# prg.net
KiCad netlist of a schematic drawn in EAGLE
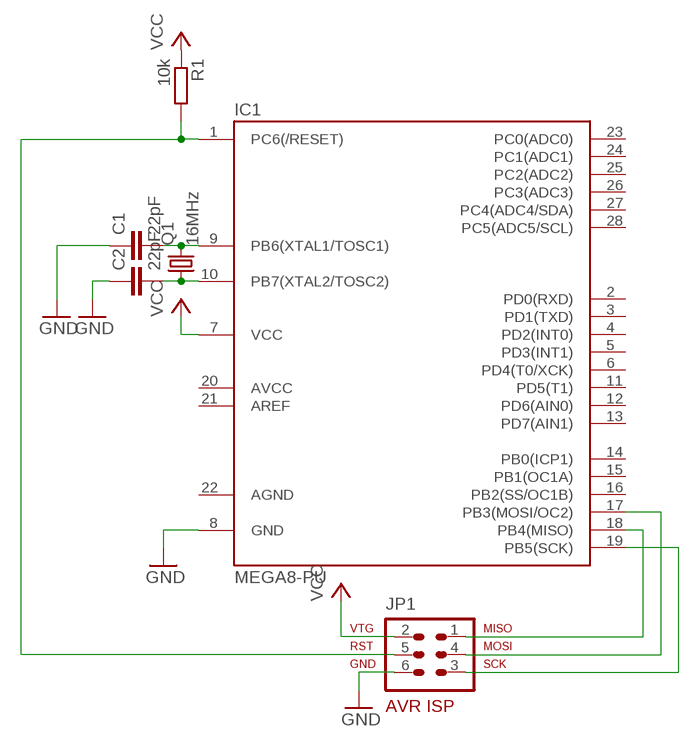
[diagram p0: schematic, sheet 1]

(export (version "E")
  (design (tool "Eeschema 10.0.6"))
  (components
    (comp (ref "C1")
      (value "22pF")
      (footprint "eagle-import:C025-025X050")
      (libsource (lib "eagle-import") (part "C-EU025-025X050"))
    )
    (comp (ref "C2")
      (value "22pF")
      (footprint "eagle-import:C050-025X075")
      (libsource (lib "eagle-import") (part "C-EU050-025X075"))
    )
    (comp (ref "IC1")
      (value "MEGA8-PU")
      (footprint "eagle-import:DIL28-3")
      (libsource (lib "eagle-import") (part "MEGA8-PU"))
    )
    (comp (ref "JP1")
      (value "AVR-ISP-6")
      (footprint "eagle-import:AVR-ISP-6")
      (libsource (lib "eagle-import") (part "AVR-ISP-6"))
    )
    (comp (ref "Q1")
      (value "16MHz")
      (footprint "eagle-import:HC49_S")
      (libsource (lib "eagle-import") (part "CRYSTALHC49S"))
    )
    (comp (ref "R1")
      (value "10k")
      (footprint "eagle-import:0204_7")
      (libsource (lib "eagle-import") (part "R-EU_0204/7"))
    )
  )
  (nets
    (net (code "1") (name "/AGND") (class "Default")
      (node (ref "IC1") (pin "22") (pinfunction "AGND_22") (pintype "power_in"))
    )
    (net (code "2") (name "GND") (class "Default")
      (node (ref "C1") (pin "1") (pinfunction "1_1") (pintype "passive"))
      (node (ref "C2") (pin "1") (pinfunction "1_1") (pintype "passive"))
      (node (ref "IC1") (pin "8") (pinfunction "GND_8") (pintype "power_in"))
      (node (ref "JP1") (pin "6") (pinfunction "6_6") (pintype "passive"))
    )
    (net (code "3") (name "Net-(IC1-PB3(MOSI{slash}OC2))") (class "Default")
      (node (ref "IC1") (pin "17") (pinfunction "PB3(MOSI/OC2)_17") (pintype "bidirectional"))
      (node (ref "JP1") (pin "4") (pinfunction "4_4") (pintype "passive"))
    )
    (net (code "4") (name "Net-(IC1-PB4(MISO))") (class "Default")
      (node (ref "IC1") (pin "18") (pinfunction "PB4(MISO)_18") (pintype "bidirectional"))
      (node (ref "JP1") (pin "1") (pinfunction "1_1") (pintype "passive"))
    )
    (net (code "5") (name "Net-(IC1-PB5(SCK))") (class "Default")
      (node (ref "IC1") (pin "19") (pinfunction "PB5(SCK)_19") (pintype "bidirectional"))
      (node (ref "JP1") (pin "3") (pinfunction "3_3") (pintype "passive"))
    )
    (net (code "6") (name "Net-(IC1-PB6(XTAL1{slash}TOSC1))") (class "Default")
      (node (ref "C1") (pin "2") (pinfunction "2_2") (pintype "passive"))
      (node (ref "IC1") (pin "9") (pinfunction "PB6(XTAL1/TOSC1)_9") (pintype "bidirectional"))
      (node (ref "Q1") (pin "2") (pinfunction "2_2") (pintype "passive"))
    )
    (net (code "7") (name "Net-(IC1-PB7(XTAL2{slash}TOSC2))") (class "Default")
      (node (ref "C2") (pin "2") (pinfunction "2_2") (pintype "passive"))
      (node (ref "IC1") (pin "10") (pinfunction "PB7(XTAL2/TOSC2)_10") (pintype "bidirectional"))
      (node (ref "Q1") (pin "1") (pinfunction "1_1") (pintype "passive"))
    )
    (net (code "8") (name "Net-(IC1-PC6({slash}RESET))") (class "Default")
      (node (ref "IC1") (pin "1") (pinfunction "PC6(/RESET)_1") (pintype "bidirectional"))
      (node (ref "JP1") (pin "5") (pinfunction "5_5") (pintype "passive"))
      (node (ref "R1") (pin "2") (pinfunction "2_2") (pintype "passive"))
    )
    (net (code "9") (name "VCC") (class "Default")
      (node (ref "IC1") (pin "7") (pinfunction "VCC_7") (pintype "power_in"))
      (node (ref "JP1") (pin "2") (pinfunction "2_2") (pintype "passive"))
      (node (ref "R1") (pin "1") (pinfunction "1_1") (pintype "passive"))
    )
    (net (code "10") (name "unconnected-(IC1-AREF-Pad21)") (class "Default")
      (node (ref "IC1") (pin "21") (pinfunction "AREF_21") (pintype "passive"))
    )
    (net (code "11") (name "unconnected-(IC1-AVCC-Pad20)") (class "Default")
      (node (ref "IC1") (pin "20") (pinfunction "AVCC_20") (pintype "passive"))
    )
    (net (code "12") (name "unconnected-(IC1-PB0(ICP1)-Pad14)") (class "Default")
      (node (ref "IC1") (pin "14") (pinfunction "PB0(ICP1)_14") (pintype "bidirectional"))
    )
    (net (code "13") (name "unconnected-(IC1-PB1(OC1A)-Pad15)") (class "Default")
      (node (ref "IC1") (pin "15") (pinfunction "PB1(OC1A)_15") (pintype "bidirectional"))
    )
    (net (code "14") (name "unconnected-(IC1-PB2(SS{slash}OC1B)-Pad16)") (class "Default")
      (node (ref "IC1") (pin "16") (pinfunction "PB2(SS/OC1B)_16") (pintype "bidirectional"))
    )
    (net (code "15") (name "unconnected-(IC1-PC0(ADC0)-Pad23)") (class "Default")
      (node (ref "IC1") (pin "23") (pinfunction "PC0(ADC0)_23") (pintype "bidirectional"))
    )
    (net (code "16") (name "unconnected-(IC1-PC1(ADC1)-Pad24)") (class "Default")
      (node (ref "IC1") (pin "24") (pinfunction "PC1(ADC1)_24") (pintype "bidirectional"))
    )
    (net (code "17") (name "unconnected-(IC1-PC2(ADC2)-Pad25)") (class "Default")
      (node (ref "IC1") (pin "25") (pinfunction "PC2(ADC2)_25") (pintype "bidirectional"))
    )
    (net (code "18") (name "unconnected-(IC1-PC3(ADC3)-Pad26)") (class "Default")
      (node (ref "IC1") (pin "26") (pinfunction "PC3(ADC3)_26") (pintype "bidirectional"))
    )
    (net (code "19") (name "unconnected-(IC1-PC4(ADC4{slash}SDA)-Pad27)") (class "Default")
      (node (ref "IC1") (pin "27") (pinfunction "PC4(ADC4/SDA)_27") (pintype "bidirectional"))
    )
    (net (code "20") (name "unconnected-(IC1-PC5(ADC5{slash}SCL)-Pad28)") (class "Default")
      (node (ref "IC1") (pin "28") (pinfunction "PC5(ADC5/SCL)_28") (pintype "bidirectional"))
    )
    (net (code "21") (name "unconnected-(IC1-PD0(RXD)-Pad2)") (class "Default")
      (node (ref "IC1") (pin "2") (pinfunction "PD0(RXD)_2") (pintype "bidirectional"))
    )
    (net (code "22") (name "unconnected-(IC1-PD1(TXD)-Pad3)") (class "Default")
      (node (ref "IC1") (pin "3") (pinfunction "PD1(TXD)_3") (pintype "bidirectional"))
    )
    (net (code "23") (name "unconnected-(IC1-PD2(INT0)-Pad4)") (class "Default")
      (node (ref "IC1") (pin "4") (pinfunction "PD2(INT0)_4") (pintype "bidirectional"))
    )
    (net (code "24") (name "unconnected-(IC1-PD3(INT1)-Pad5)") (class "Default")
      (node (ref "IC1") (pin "5") (pinfunction "PD3(INT1)_5") (pintype "bidirectional"))
    )
    (net (code "25") (name "unconnected-(IC1-PD4(T0{slash}XCK)-Pad6)") (class "Default")
      (node (ref "IC1") (pin "6") (pinfunction "PD4(T0/XCK)_6") (pintype "bidirectional"))
    )
    (net (code "26") (name "unconnected-(IC1-PD5(T1)-Pad11)") (class "Default")
      (node (ref "IC1") (pin "11") (pinfunction "PD5(T1)_11") (pintype "bidirectional"))
    )
    (net (code "27") (name "unconnected-(IC1-PD6(AIN0)-Pad12)") (class "Default")
      (node (ref "IC1") (pin "12") (pinfunction "PD6(AIN0)_12") (pintype "bidirectional"))
    )
    (net (code "28") (name "unconnected-(IC1-PD7(AIN1)-Pad13)") (class "Default")
      (node (ref "IC1") (pin "13") (pinfunction "PD7(AIN1)_13") (pintype "bidirectional"))
    )
  )
)
